# ICM42688-P.net
KiCad netlist of a schematic drawn in EasyEDA Pro
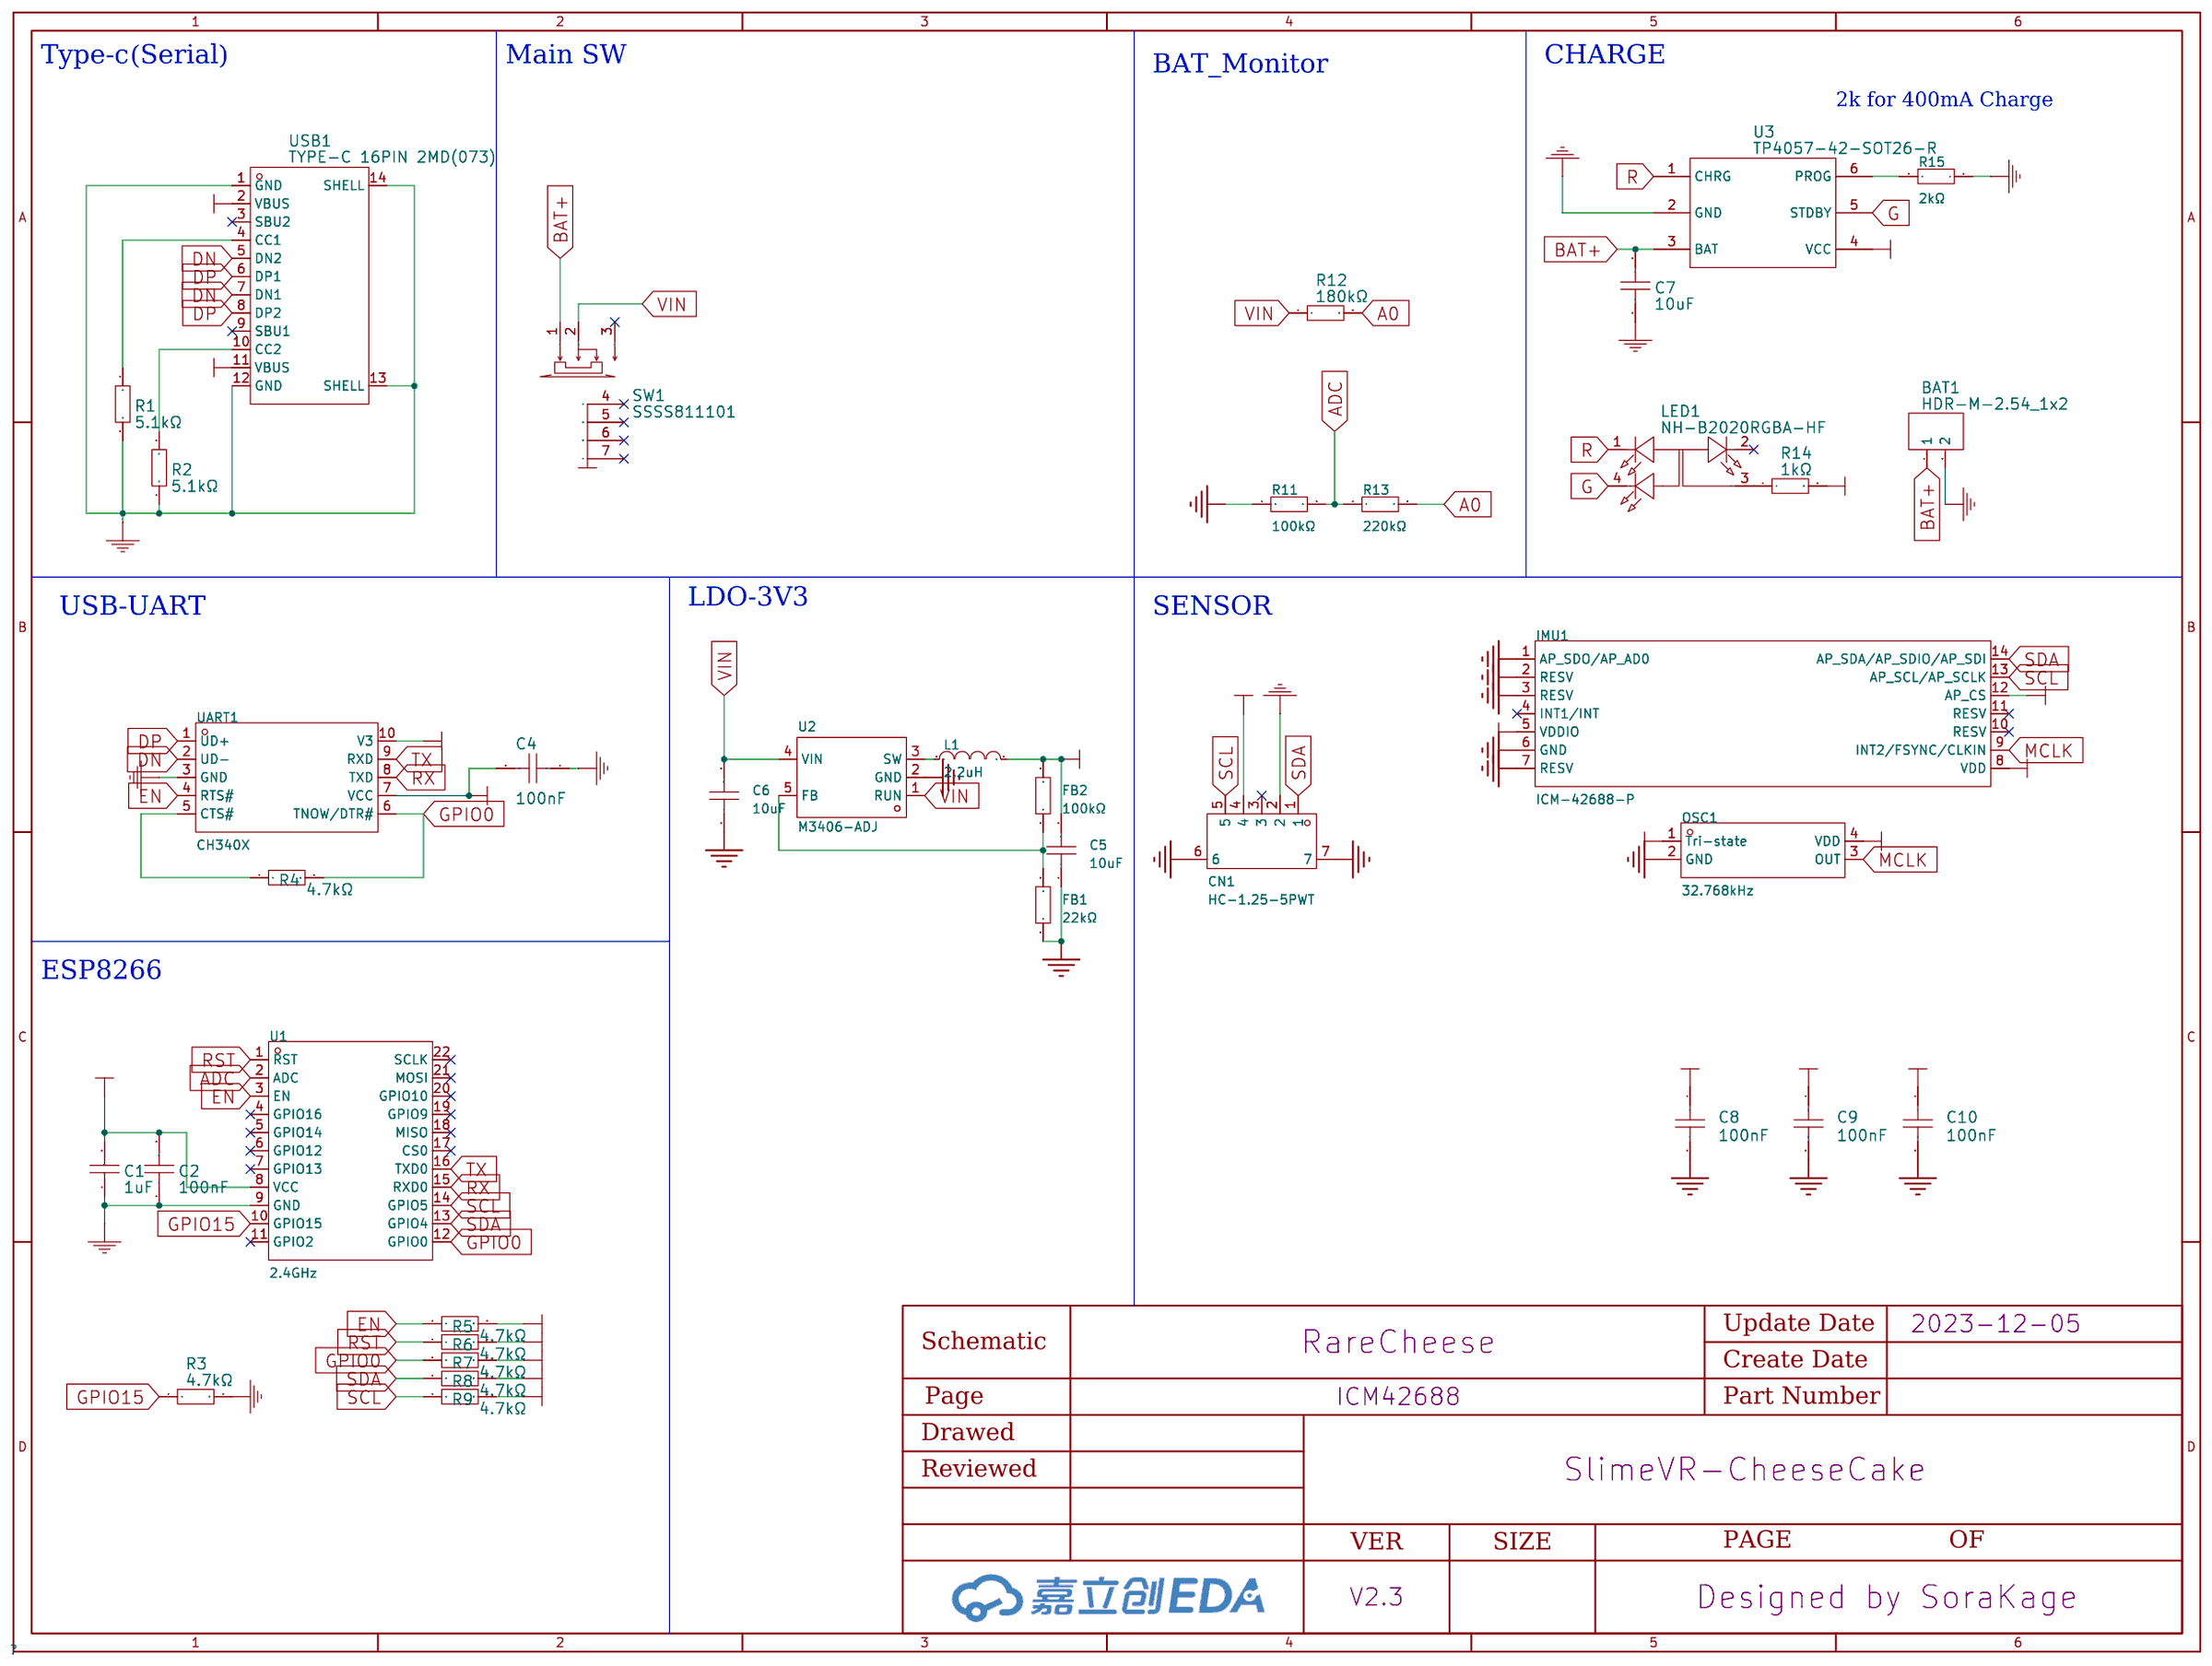
[diagram p0: schematic sheet]

(export (version "E")
  (design (tool "Eeschema 10.0.6"))
  (components
    (comp (ref "BAT1")
      (value "HDR-M-2.54_1x2")
      (footprint "easyedapro:HDR-M-2.54_1X2")
      (libsource (lib "easyedapro") (part "HDR-M-2.54_1x2"))
    )
    (comp (ref "C1")
      (value "1uF")
      (footprint "easyedapro:C0603")
      (fields
        (field (name "Manufacturer Part") "CL10A105KB8NNNC")
        (field (name "Manufacturer") "SAMSUNG(三星)")
      )
      (libsource (lib "easyedapro") (part "1uF"))
    )
    (comp (ref "C2")
      (value "100nF")
      (footprint "easyedapro:C0603")
      (fields
        (field (name "Manufacturer Part") "CC0603KRX7R9BB104")
        (field (name "Manufacturer") "YAGEO(国巨)")
      )
      (libsource (lib "easyedapro") (part "100nF"))
    )
    (comp (ref "C4")
      (value "100nF")
      (footprint "easyedapro:C0603")
      (fields
        (field (name "Manufacturer Part") "CC0603KRX7R9BB104")
        (field (name "Manufacturer") "YAGEO(国巨)")
      )
      (libsource (lib "easyedapro") (part "100nF"))
    )
    (comp (ref "C5")
      (value "10uF")
      (footprint "easyedapro:C0603")
      (description "容值:10uF;精度:±10%;额定电压:10V;材质(温度系数):X5R;")
      (fields
        (field (name "Manufacturer Part") "CL10A106KP8NNNC")
        (field (name "Manufacturer") "SAMSUNG(三星)")
      )
      (libsource (lib "easyedapro") (part "CL10A106KP8NNNC"))
    )
    (comp (ref "C6")
      (value "10uF")
      (footprint "easyedapro:C0603")
      (description "容值:10uF;精度:±10%;额定电压:10V;材质(温度系数):X5R;")
      (fields
        (field (name "Manufacturer Part") "CL10A106KP8NNNC")
        (field (name "Manufacturer") "SAMSUNG(三星)")
      )
      (libsource (lib "easyedapro") (part "CL10A106KP8NNNC"))
    )
    (comp (ref "C7")
      (value "10uF")
      (footprint "easyedapro:C0603")
      (fields
        (field (name "Manufacturer Part") "CL10A106KP8NNNC")
        (field (name "Manufacturer") "SAMSUNG(三星)")
      )
      (libsource (lib "easyedapro") (part "10uF"))
    )
    (comp (ref "C8")
      (value "100nF")
      (footprint "easyedapro:C0603")
      (fields
        (field (name "Manufacturer Part") "CC0603KRX7R9BB104")
        (field (name "Manufacturer") "YAGEO(国巨)")
      )
      (libsource (lib "easyedapro") (part "100nF"))
    )
    (comp (ref "C9")
      (value "100nF")
      (footprint "easyedapro:C0603")
      (fields
        (field (name "Manufacturer Part") "CC0603KRX7R9BB104")
        (field (name "Manufacturer") "YAGEO(国巨)")
      )
      (libsource (lib "easyedapro") (part "100nF"))
    )
    (comp (ref "C10")
      (value "100nF")
      (footprint "easyedapro:C0603")
      (fields
        (field (name "Manufacturer Part") "CC0603KRX7R9BB104")
        (field (name "Manufacturer") "YAGEO(国巨)")
      )
      (libsource (lib "easyedapro") (part "100nF"))
    )
    (comp (ref "CN1")
      (value "HC-1.25-5PWT")
      (footprint "easyedapro:CONN-SMD_5P-P1.25_HCTL_HC-1.25-5PWT")
      (description "参考系列:-;间距:1.25mm;插针结构:1x5P;排数:1;每排PIN数:5;行距:-;公母:公型插针;安装方式:卧贴;额定电流:1A;工作温度范围:-25°C~+85°C;")
      (fields (field (name "Manufacturer") "HCTL(华灿天禄)"))
      (libsource (lib "easyedapro") (part "HC-1.25-5PWT"))
    )
    (comp (ref "FB1")
      (value "22kΩ")
      (footprint "easyedapro:R0402")
      (description "电阻类型:厚膜电阻;阻值:22kΩ;精度:±1%;功率:62.5mW;")
      (fields
        (field (name "Manufacturer Part") "0402WGF2202TCE")
        (field (name "Manufacturer") "UNI-ROYAL(厚声)")
      )
      (libsource (lib "easyedapro") (part "0402WGF2202TCE"))
    )
    (comp (ref "FB2")
      (value "100kΩ")
      (footprint "easyedapro:R0402")
      (description "电阻类型:厚膜电阻;阻值:100kΩ;精度:±1%;功率:62.5mW;")
      (fields
        (field (name "Manufacturer Part") "0402WGF1003TCE")
        (field (name "Manufacturer") "UNI-ROYAL(厚声)")
      )
      (libsource (lib "easyedapro") (part "0402WGF1003TCE"))
    )
    (comp (ref "IMU1")
      (value "ICM-42688-P")
      (footprint "easyedapro:LGA-14_L3.0-W2.5-P0.50-TL")
      (fields (field (name "Manufacturer") "TDK InvenSense(应美盛)"))
      (libsource (lib "easyedapro") (part "ICM-42688-P"))
    )
    (comp (ref "L1")
      (value "2.2uH")
      (footprint "easyedapro:IND-SMD_L2.5-W2.0_YXMBL252010P")
      (description "类型:一体成型电感;电感值:2.2uH;精度:±20%;额定电流:2.1A;饱和电流(Isat):3A;")
      (fields (field (name "Manufacturer Part") "APH252010T2R2M") (field (name "Manufacturer") "APV(爱普微)"))
      (libsource (lib "easyedapro") (part "APH252010T2R2M"))
    )
    (comp (ref "LED1")
      (value "NH-B2020RGBA-HF")
      (footprint "easyedapro:LED-ARRAY-SMD_4P-L2.1-W2.1-TL_NH-B2020RGBA")
      (fields (field (name "Manufacturer") "国星光电"))
      (libsource (lib "easyedapro") (part "NH-B2020RGBA-HF"))
    )
    (comp (ref "OSC1")
      (value "32.768kHz")
      (footprint "easyedapro:OSC-SMD_4P-L3.2-W2.5-BL")
      (description "频率:32.768kHz;工作电压:1.8V~3.3V;")
      (fields
        (field (name "Manufacturer Part") "OK2EL89CJI-111YLC-32.768K")
        (field (name "Manufacturer") "YXC(扬兴晶振)")
      )
      (libsource (lib "easyedapro") (part "OK2EL89CJI-111YLC-32.768K"))
    )
    (comp (ref "R1")
      (value "5.1kΩ")
      (footprint "easyedapro:R0603")
      (fields
        (field (name "Manufacturer Part") "0603WAF5101T5E")
        (field (name "Manufacturer") "UNI-ROYAL(厚声)")
      )
      (libsource (lib "easyedapro") (part "5.1kΩ"))
    )
    (comp (ref "R2")
      (value "5.1kΩ")
      (footprint "easyedapro:R0603")
      (fields
        (field (name "Manufacturer Part") "0603WAF5101T5E")
        (field (name "Manufacturer") "UNI-ROYAL(厚声)")
      )
      (libsource (lib "easyedapro") (part "5.1kΩ"))
    )
    (comp (ref "R3")
      (value "4.7kΩ")
      (footprint "easyedapro:R0603")
      (fields
        (field (name "Manufacturer Part") "0603WAF4701T5E")
        (field (name "Manufacturer") "UNI-ROYAL(厚声)")
      )
      (libsource (lib "easyedapro") (part "4.7kΩ"))
    )
    (comp (ref "R4")
      (value "4.7kΩ")
      (footprint "easyedapro:R0603")
      (fields
        (field (name "Manufacturer Part") "0603WAF4701T5E")
        (field (name "Manufacturer") "UNI-ROYAL(厚声)")
      )
      (libsource (lib "easyedapro") (part "4.7kΩ"))
    )
    (comp (ref "R5")
      (value "4.7kΩ")
      (footprint "easyedapro:R0603")
      (fields
        (field (name "Manufacturer Part") "0603WAF4701T5E")
        (field (name "Manufacturer") "UNI-ROYAL(厚声)")
      )
      (libsource (lib "easyedapro") (part "4.7kΩ"))
    )
    (comp (ref "R6")
      (value "4.7kΩ")
      (footprint "easyedapro:R0603")
      (fields
        (field (name "Manufacturer Part") "0603WAF4701T5E")
        (field (name "Manufacturer") "UNI-ROYAL(厚声)")
      )
      (libsource (lib "easyedapro") (part "4.7kΩ"))
    )
    (comp (ref "R7")
      (value "4.7kΩ")
      (footprint "easyedapro:R0603")
      (fields
        (field (name "Manufacturer Part") "0603WAF4701T5E")
        (field (name "Manufacturer") "UNI-ROYAL(厚声)")
      )
      (libsource (lib "easyedapro") (part "4.7kΩ"))
    )
    (comp (ref "R8")
      (value "4.7kΩ")
      (footprint "easyedapro:R0603")
      (fields
        (field (name "Manufacturer Part") "0603WAF4701T5E")
        (field (name "Manufacturer") "UNI-ROYAL(厚声)")
      )
      (libsource (lib "easyedapro") (part "4.7kΩ"))
    )
    (comp (ref "R9")
      (value "4.7kΩ")
      (footprint "easyedapro:R0603")
      (fields
        (field (name "Manufacturer Part") "0603WAF4701T5E")
        (field (name "Manufacturer") "UNI-ROYAL(厚声)")
      )
      (libsource (lib "easyedapro") (part "4.7kΩ"))
    )
    (comp (ref "R11")
      (value "100kΩ")
      (footprint "easyedapro:R0603")
      (description "电阻类型:厚膜电阻;阻值:100kΩ;精度:±1%;功率:100mW;")
      (fields
        (field (name "Manufacturer Part") "0603WAF1003T5E")
        (field (name "Manufacturer") "UNI-ROYAL(厚声)")
      )
      (libsource (lib "easyedapro") (part "0603WAF1003T5E"))
    )
    (comp (ref "R12")
      (value "180kΩ")
      (footprint "easyedapro:R0603")
      (fields
        (field (name "Manufacturer Part") "0603WAF1803T5E")
        (field (name "Manufacturer") "UNI-ROYAL(厚声)")
      )
      (libsource (lib "easyedapro") (part "180kΩ"))
    )
    (comp (ref "R13")
      (value "220kΩ")
      (footprint "easyedapro:R0603")
      (description "电阻类型:厚膜电阻;阻值:220kΩ;精度:±1%;功率:100mW;")
      (fields
        (field (name "Manufacturer Part") "0603WAF2203T5E")
        (field (name "Manufacturer") "UNI-ROYAL(厚声)")
      )
      (libsource (lib "easyedapro") (part "0603WAF2203T5E"))
    )
    (comp (ref "R14")
      (value "1kΩ")
      (footprint "easyedapro:R0603")
      (fields
        (field (name "Manufacturer Part") "0603WAF1001T5E")
        (field (name "Manufacturer") "UNI-ROYAL(厚声)")
      )
      (libsource (lib "easyedapro") (part "1kΩ"))
    )
    (comp (ref "R15")
      (value "2kΩ")
      (footprint "easyedapro:R0603")
      (description "电阻类型:厚膜电阻;阻值:2kΩ;精度:±1%;功率:100mW;")
      (fields
        (field (name "Manufacturer Part") "0603WAF2001T5E")
        (field (name "Manufacturer") "UNI-ROYAL(厚声)")
      )
      (libsource (lib "easyedapro") (part "0603WAF2001T5E"))
    )
    (comp (ref "SW1")
      (value "SSSS811101")
      (footprint "easyedapro:SW-SMD_SSSS811101")
      (fields (field (name "Manufacturer") "ALPSALPINE(阿尔卑斯阿尔派)"))
      (libsource (lib "easyedapro") (part "SSSS811101"))
    )
    (comp (ref "U1")
      (value "2.4GHz")
      (footprint "easyedapro:WIFIM-SMD_ESP-12F-ESP8266MOD")
      (description "频率:2.4GHz;发射功率:16dBm;核心处理器:ESP8266;天线形式:PCB 板载天线;接收灵敏度:-90dBm;")
      (fields
        (field (name "Manufacturer Part") "ESP-12F(ESP8266MOD)")
        (field (name "Manufacturer") "Ai-Thinker(安信可)")
      )
      (libsource (lib "easyedapro") (part "ESP-12F(ESP8266MOD)"))
    )
    (comp (ref "U2")
      (value "M3406-ADJ")
      (footprint "easyedapro:SOT-23-5_L3.0-W1.7-P0.95-LS2.8-BR")
      (description "功能类型:降压型;同步整流:-;输出通道数:-;拓扑结构:-;输入电压:-;输出电流(最大值):-;开关频率:-;")
      (fields (field (name "Manufacturer") "西安航天民芯"))
      (libsource (lib "easyedapro") (part "M3406"))
    )
    (comp (ref "U3")
      (value "TP4057-42-SOT26-R")
      (footprint "easyedapro:SOT-23-6_L2.9-W1.6-P0.95-LS2.8-BL")
      (fields (field (name "Manufacturer") "TOPPOWER(南京拓微)"))
      (libsource (lib "easyedapro") (part "TP4057"))
    )
    (comp (ref "UART1")
      (value "CH340X")
      (footprint "easyedapro:MSOP-10_L3.0-W3.0-P0.50-LS5.0-BL")
      (fields (field (name "Manufacturer") "WCH(南京沁恒)"))
      (libsource (lib "easyedapro") (part "CH340X"))
    )
    (comp (ref "USB1")
      (value "TYPE-C 16PIN 2MD(073)")
      (footprint "easyedapro:USB-C-SMD_TYPE-C-6PIN-2MD-073")
      (fields (field (name "Manufacturer") "SHOU HAN(首韩)"))
      (libsource (lib "easyedapro") (part "TYPE-C 16PIN 2MD(073)"))
    )
  )
  (nets
    (net (code "1") (name "+5V") (class "Default")
      (node (ref "R14") (pin "2") (pinfunction "2_2") (pintype "input"))
      (node (ref "U3") (pin "4") (pinfunction "VCC_4") (pintype "unspecified"))
      (node (ref "USB1") (pin "11") (pinfunction "VBUS_11") (pintype "input"))
      (node (ref "USB1") (pin "2") (pinfunction "VBUS_2") (pintype "input"))
    )
    (net (code "2") (name "3V3") (class "Default")
      (node (ref "C1") (pin "2") (pinfunction "2_2") (pintype "input"))
      (node (ref "C10") (pin "1") (pinfunction "1_1") (pintype "input"))
      (node (ref "C2") (pin "2") (pinfunction "2_2") (pintype "input"))
      (node (ref "C4") (pin "2") (pinfunction "2_2") (pintype "input"))
      (node (ref "C5") (pin "2") (pinfunction "2_2") (pintype "unspecified"))
      (node (ref "C8") (pin "1") (pinfunction "1_1") (pintype "input"))
      (node (ref "C9") (pin "1") (pinfunction "1_1") (pintype "input"))
      (node (ref "CN1") (pin "4") (pinfunction "4_4") (pintype "unspecified"))
      (node (ref "FB2") (pin "2") (pinfunction "2_2") (pintype "input"))
      (node (ref "IMU1") (pin "12") (pinfunction "AP_CS_12") (pintype "input"))
      (node (ref "IMU1") (pin "5") (pinfunction "VDDIO_5") (pintype "input"))
      (node (ref "IMU1") (pin "8") (pinfunction "VDD_8") (pintype "input"))
      (node (ref "L1") (pin "2") (pinfunction "2_2") (pintype "unspecified"))
      (node (ref "OSC1") (pin "1") (pinfunction "Tri-state_1") (pintype "unspecified"))
      (node (ref "OSC1") (pin "4") (pinfunction "VDD_4") (pintype "unspecified"))
      (node (ref "R5") (pin "2") (pinfunction "2_2") (pintype "input"))
      (node (ref "R6") (pin "2") (pinfunction "2_2") (pintype "input"))
      (node (ref "R7") (pin "2") (pinfunction "2_2") (pintype "input"))
      (node (ref "R8") (pin "2") (pinfunction "2_2") (pintype "input"))
      (node (ref "R9") (pin "2") (pinfunction "2_2") (pintype "input"))
      (node (ref "U1") (pin "8") (pinfunction "VCC_8") (pintype "input"))
      (node (ref "UART1") (pin "10") (pinfunction "V3_10") (pintype "unspecified"))
      (node (ref "UART1") (pin "7") (pinfunction "VCC_7") (pintype "unspecified"))
    )
    (net (code "3") (name "A0") (class "Default")
      (node (ref "R12") (pin "2") (pinfunction "2_2") (pintype "input"))
      (node (ref "R13") (pin "2") (pinfunction "2_2") (pintype "input"))
    )
    (net (code "4") (name "ADC") (class "Default")
      (node (ref "R11") (pin "2") (pinfunction "2_2") (pintype "input"))
      (node (ref "R13") (pin "1") (pinfunction "1_1") (pintype "input"))
      (node (ref "U1") (pin "2") (pinfunction "ADC_2") (pintype "input"))
    )
    (net (code "5") (name "BAT+") (class "Default")
      (node (ref "BAT1") (pin "1") (pinfunction "1_1") (pintype "input"))
      (node (ref "C7") (pin "2") (pinfunction "2_2") (pintype "input"))
      (node (ref "SW1") (pin "1") (pinfunction "1_1") (pintype "input"))
      (node (ref "U3") (pin "3") (pinfunction "BAT_3") (pintype "unspecified"))
    )
    (net (code "6") (name "DN") (class "Default")
      (node (ref "UART1") (pin "2") (pinfunction "UD-_2") (pintype "unspecified"))
      (node (ref "USB1") (pin "5") (pinfunction "DN2_5") (pintype "input"))
      (node (ref "USB1") (pin "7") (pinfunction "DN1_7") (pintype "input"))
    )
    (net (code "7") (name "DP") (class "Default")
      (node (ref "UART1") (pin "1") (pinfunction "UD+_1") (pintype "unspecified"))
      (node (ref "USB1") (pin "6") (pinfunction "DP1_6") (pintype "input"))
      (node (ref "USB1") (pin "8") (pinfunction "DP2_8") (pintype "input"))
    )
    (net (code "8") (name "EN") (class "Default")
      (node (ref "R5") (pin "1") (pinfunction "1_1") (pintype "input"))
      (node (ref "U1") (pin "3") (pinfunction "EN_3") (pintype "input"))
      (node (ref "UART1") (pin "4") (pinfunction "RTS#_4") (pintype "unspecified"))
    )
    (net (code "9") (name "G") (class "Default")
      (node (ref "LED1") (pin "4") (pinfunction "-_4") (pintype "input"))
      (node (ref "U3") (pin "5") (pinfunction "STDBY_5") (pintype "unspecified"))
    )
    (net (code "10") (name "GND") (class "Default")
      (node (ref "BAT1") (pin "2") (pinfunction "2_2") (pintype "input"))
      (node (ref "C1") (pin "1") (pinfunction "1_1") (pintype "input"))
      (node (ref "C10") (pin "2") (pinfunction "2_2") (pintype "input"))
      (node (ref "C2") (pin "1") (pinfunction "1_1") (pintype "input"))
      (node (ref "C4") (pin "1") (pinfunction "1_1") (pintype "input"))
      (node (ref "C5") (pin "1") (pinfunction "1_1") (pintype "unspecified"))
      (node (ref "C6") (pin "1") (pinfunction "1_1") (pintype "unspecified"))
      (node (ref "C7") (pin "1") (pinfunction "1_1") (pintype "input"))
      (node (ref "C8") (pin "2") (pinfunction "2_2") (pintype "input"))
      (node (ref "C9") (pin "2") (pinfunction "2_2") (pintype "input"))
      (node (ref "CN1") (pin "2") (pinfunction "2_2") (pintype "unspecified"))
      (node (ref "CN1") (pin "6") (pinfunction "6_6") (pintype "unspecified"))
      (node (ref "CN1") (pin "7") (pinfunction "7_7") (pintype "unspecified"))
      (node (ref "FB1") (pin "1") (pinfunction "1_1") (pintype "input"))
      (node (ref "IMU1") (pin "1") (pinfunction "AP_SDO/AP_AD0_1") (pintype "input"))
      (node (ref "IMU1") (pin "2") (pinfunction "RESV_2") (pintype "input"))
      (node (ref "IMU1") (pin "3") (pinfunction "RESV_3") (pintype "input"))
      (node (ref "IMU1") (pin "6") (pinfunction "GND_6") (pintype "input"))
      (node (ref "IMU1") (pin "7") (pinfunction "RESV_7") (pintype "input"))
      (node (ref "OSC1") (pin "2") (pinfunction "GND_2") (pintype "unspecified"))
      (node (ref "R1") (pin "1") (pinfunction "1_1") (pintype "input"))
      (node (ref "R11") (pin "1") (pinfunction "1_1") (pintype "input"))
      (node (ref "R15") (pin "2") (pinfunction "2_2") (pintype "input"))
      (node (ref "R2") (pin "1") (pinfunction "1_1") (pintype "input"))
      (node (ref "R3") (pin "2") (pinfunction "2_2") (pintype "input"))
      (node (ref "U1") (pin "9") (pinfunction "GND_9") (pintype "input"))
      (node (ref "U2") (pin "2") (pinfunction "GND_2") (pintype "input"))
      (node (ref "U3") (pin "2") (pinfunction "GND_2") (pintype "unspecified"))
      (node (ref "UART1") (pin "3") (pinfunction "GND_3") (pintype "unspecified"))
      (node (ref "USB1") (pin "1") (pinfunction "GND_1") (pintype "input"))
      (node (ref "USB1") (pin "12") (pinfunction "GND_12") (pintype "input"))
      (node (ref "USB1") (pin "13") (pinfunction "SHELL_13") (pintype "input"))
      (node (ref "USB1") (pin "14") (pinfunction "SHELL_14") (pintype "input"))
    )
    (net (code "11") (name "GPIO0") (class "Default")
      (node (ref "R4") (pin "2") (pinfunction "2_2") (pintype "input"))
      (node (ref "R7") (pin "1") (pinfunction "1_1") (pintype "input"))
      (node (ref "U1") (pin "12") (pinfunction "GPIO0_12") (pintype "input"))
      (node (ref "UART1") (pin "6") (pinfunction "TNOW/DTR#_6") (pintype "unspecified"))
    )
    (net (code "12") (name "GPIO15") (class "Default")
      (node (ref "R3") (pin "1") (pinfunction "1_1") (pintype "input"))
      (node (ref "U1") (pin "10") (pinfunction "GPIO15_10") (pintype "input"))
    )
    (net (code "13") (name "MCLK") (class "Default")
      (node (ref "IMU1") (pin "9") (pinfunction "INT2/FSYNC/CLKIN_9") (pintype "input"))
      (node (ref "OSC1") (pin "3") (pinfunction "OUT_3") (pintype "unspecified"))
    )
    (net (code "14") (name "Net-(LED1-+)") (class "Default")
      (node (ref "LED1") (pin "3") (pinfunction "+_3") (pintype "input"))
      (node (ref "R14") (pin "1") (pinfunction "1_1") (pintype "input"))
    )
    (net (code "15") (name "Net-(U2-FB)") (class "Default")
      (node (ref "FB1") (pin "2") (pinfunction "2_2") (pintype "input"))
      (node (ref "FB2") (pin "1") (pinfunction "1_1") (pintype "input"))
      (node (ref "U2") (pin "5") (pinfunction "FB_5") (pintype "input"))
    )
    (net (code "16") (name "Net-(U2-SW)") (class "Default")
      (node (ref "L1") (pin "1") (pinfunction "1_1") (pintype "unspecified"))
      (node (ref "U2") (pin "3") (pinfunction "SW_3") (pintype "input"))
    )
    (net (code "17") (name "Net-(U3-PROG)") (class "Default")
      (node (ref "R15") (pin "1") (pinfunction "1_1") (pintype "input"))
      (node (ref "U3") (pin "6") (pinfunction "PROG_6") (pintype "unspecified"))
    )
    (net (code "18") (name "Net-(UART1-CTS#)") (class "Default")
      (node (ref "R4") (pin "1") (pinfunction "1_1") (pintype "input"))
      (node (ref "UART1") (pin "5") (pinfunction "CTS#_5") (pintype "unspecified"))
    )
    (net (code "19") (name "Net-(USB1-CC1)") (class "Default")
      (node (ref "R1") (pin "2") (pinfunction "2_2") (pintype "input"))
      (node (ref "USB1") (pin "4") (pinfunction "CC1_4") (pintype "input"))
    )
    (net (code "20") (name "Net-(USB1-CC2)") (class "Default")
      (node (ref "R2") (pin "2") (pinfunction "2_2") (pintype "input"))
      (node (ref "USB1") (pin "10") (pinfunction "CC2_10") (pintype "input"))
    )
    (net (code "21") (name "R") (class "Default")
      (node (ref "LED1") (pin "1") (pinfunction "-_1") (pintype "input"))
      (node (ref "U3") (pin "1") (pinfunction "CHRG_1") (pintype "unspecified"))
    )
    (net (code "22") (name "RST") (class "Default")
      (node (ref "R6") (pin "1") (pinfunction "1_1") (pintype "input"))
      (node (ref "U1") (pin "1") (pinfunction "RST_1") (pintype "input"))
    )
    (net (code "23") (name "RX") (class "Default")
      (node (ref "U1") (pin "15") (pinfunction "RXD0_15") (pintype "input"))
      (node (ref "UART1") (pin "8") (pinfunction "TXD_8") (pintype "unspecified"))
    )
    (net (code "24") (name "SCL") (class "Default")
      (node (ref "CN1") (pin "5") (pinfunction "5_5") (pintype "unspecified"))
      (node (ref "IMU1") (pin "13") (pinfunction "AP_SCL/AP_SCLK_13") (pintype "input"))
      (node (ref "R9") (pin "1") (pinfunction "1_1") (pintype "input"))
      (node (ref "U1") (pin "14") (pinfunction "GPIO5_14") (pintype "input"))
    )
    (net (code "25") (name "SDA") (class "Default")
      (node (ref "CN1") (pin "1") (pinfunction "1_1") (pintype "unspecified"))
      (node (ref "IMU1") (pin "14") (pinfunction "AP_SDA/AP_SDIO/AP_SDI_14") (pintype "input"))
      (node (ref "R8") (pin "1") (pinfunction "1_1") (pintype "input"))
      (node (ref "U1") (pin "13") (pinfunction "GPIO4_13") (pintype "input"))
    )
    (net (code "26") (name "TX") (class "Default")
      (node (ref "U1") (pin "16") (pinfunction "TXD0_16") (pintype "input"))
      (node (ref "UART1") (pin "9") (pinfunction "RXD_9") (pintype "unspecified"))
    )
    (net (code "27") (name "VIN") (class "Default")
      (node (ref "C6") (pin "2") (pinfunction "2_2") (pintype "unspecified"))
      (node (ref "R12") (pin "1") (pinfunction "1_1") (pintype "input"))
      (node (ref "SW1") (pin "2") (pinfunction "2_2") (pintype "input"))
      (node (ref "U2") (pin "1") (pinfunction "RUN_1") (pintype "input"))
      (node (ref "U2") (pin "4") (pinfunction "VIN_4") (pintype "input"))
    )
    (net (code "28") (name "unconnected-(CN1-Pad3)") (class "Default")
      (node (ref "CN1") (pin "3") (pinfunction "3_3") (pintype "unspecified+no_connect"))
    )
    (net (code "29") (name "unconnected-(IMU1-INT1{slash}INT-Pad4)") (class "Default")
      (node (ref "IMU1") (pin "4") (pinfunction "INT1/INT_4") (pintype "input+no_connect"))
    )
    (net (code "30") (name "unconnected-(IMU1-RESV-Pad10)") (class "Default")
      (node (ref "IMU1") (pin "10") (pinfunction "RESV_10") (pintype "input+no_connect"))
    )
    (net (code "31") (name "unconnected-(IMU1-RESV-Pad11)") (class "Default")
      (node (ref "IMU1") (pin "11") (pinfunction "RESV_11") (pintype "input+no_connect"))
    )
    (net (code "32") (name "unconnected-(LED1---Pad2)") (class "Default")
      (node (ref "LED1") (pin "2") (pinfunction "-_2") (pintype "input+no_connect"))
    )
    (net (code "33") (name "unconnected-(SW1-Pad3)") (class "Default")
      (node (ref "SW1") (pin "3") (pinfunction "3_3") (pintype "input+no_connect"))
    )
    (net (code "34") (name "unconnected-(SW1-Pad4)") (class "Default")
      (node (ref "SW1") (pin "4") (pinfunction "4_4") (pintype "input+no_connect"))
    )
    (net (code "35") (name "unconnected-(SW1-Pad5)") (class "Default")
      (node (ref "SW1") (pin "5") (pinfunction "5_5") (pintype "input+no_connect"))
    )
    (net (code "36") (name "unconnected-(SW1-Pad6)") (class "Default")
      (node (ref "SW1") (pin "6") (pinfunction "6_6") (pintype "input+no_connect"))
    )
    (net (code "37") (name "unconnected-(SW1-Pad7)") (class "Default")
      (node (ref "SW1") (pin "7") (pinfunction "7_7") (pintype "input+no_connect"))
    )
    (net (code "38") (name "unconnected-(U1-CS0-Pad17)") (class "Default")
      (node (ref "U1") (pin "17") (pinfunction "CS0_17") (pintype "input+no_connect"))
    )
    (net (code "39") (name "unconnected-(U1-GPIO2-Pad11)") (class "Default")
      (node (ref "U1") (pin "11") (pinfunction "GPIO2_11") (pintype "input+no_connect"))
    )
    (net (code "40") (name "unconnected-(U1-GPIO9-Pad19)") (class "Default")
      (node (ref "U1") (pin "19") (pinfunction "GPIO9_19") (pintype "input+no_connect"))
    )
    (net (code "41") (name "unconnected-(U1-GPIO10-Pad20)") (class "Default")
      (node (ref "U1") (pin "20") (pinfunction "GPIO10_20") (pintype "input+no_connect"))
    )
    (net (code "42") (name "unconnected-(U1-GPIO12-Pad6)") (class "Default")
      (node (ref "U1") (pin "6") (pinfunction "GPIO12_6") (pintype "input+no_connect"))
    )
    (net (code "43") (name "unconnected-(U1-GPIO13-Pad7)") (class "Default")
      (node (ref "U1") (pin "7") (pinfunction "GPIO13_7") (pintype "input+no_connect"))
    )
    (net (code "44") (name "unconnected-(U1-GPIO14-Pad5)") (class "Default")
      (node (ref "U1") (pin "5") (pinfunction "GPIO14_5") (pintype "input+no_connect"))
    )
    (net (code "45") (name "unconnected-(U1-GPIO16-Pad4)") (class "Default")
      (node (ref "U1") (pin "4") (pinfunction "GPIO16_4") (pintype "input+no_connect"))
    )
    (net (code "46") (name "unconnected-(U1-MISO-Pad18)") (class "Default")
      (node (ref "U1") (pin "18") (pinfunction "MISO_18") (pintype "input+no_connect"))
    )
    (net (code "47") (name "unconnected-(U1-MOSI-Pad21)") (class "Default")
      (node (ref "U1") (pin "21") (pinfunction "MOSI_21") (pintype "input+no_connect"))
    )
    (net (code "48") (name "unconnected-(U1-SCLK-Pad22)") (class "Default")
      (node (ref "U1") (pin "22") (pinfunction "SCLK_22") (pintype "input+no_connect"))
    )
    (net (code "49") (name "unconnected-(USB1-SBU1-Pad9)") (class "Default")
      (node (ref "USB1") (pin "9") (pinfunction "SBU1_9") (pintype "input+no_connect"))
    )
    (net (code "50") (name "unconnected-(USB1-SBU2-Pad3)") (class "Default")
      (node (ref "USB1") (pin "3") (pinfunction "SBU2_3") (pintype "input+no_connect"))
    )
  )
)
